# 16_VibrationdriverMod.net
KiCad netlist of a schematic drawn in EAGLE
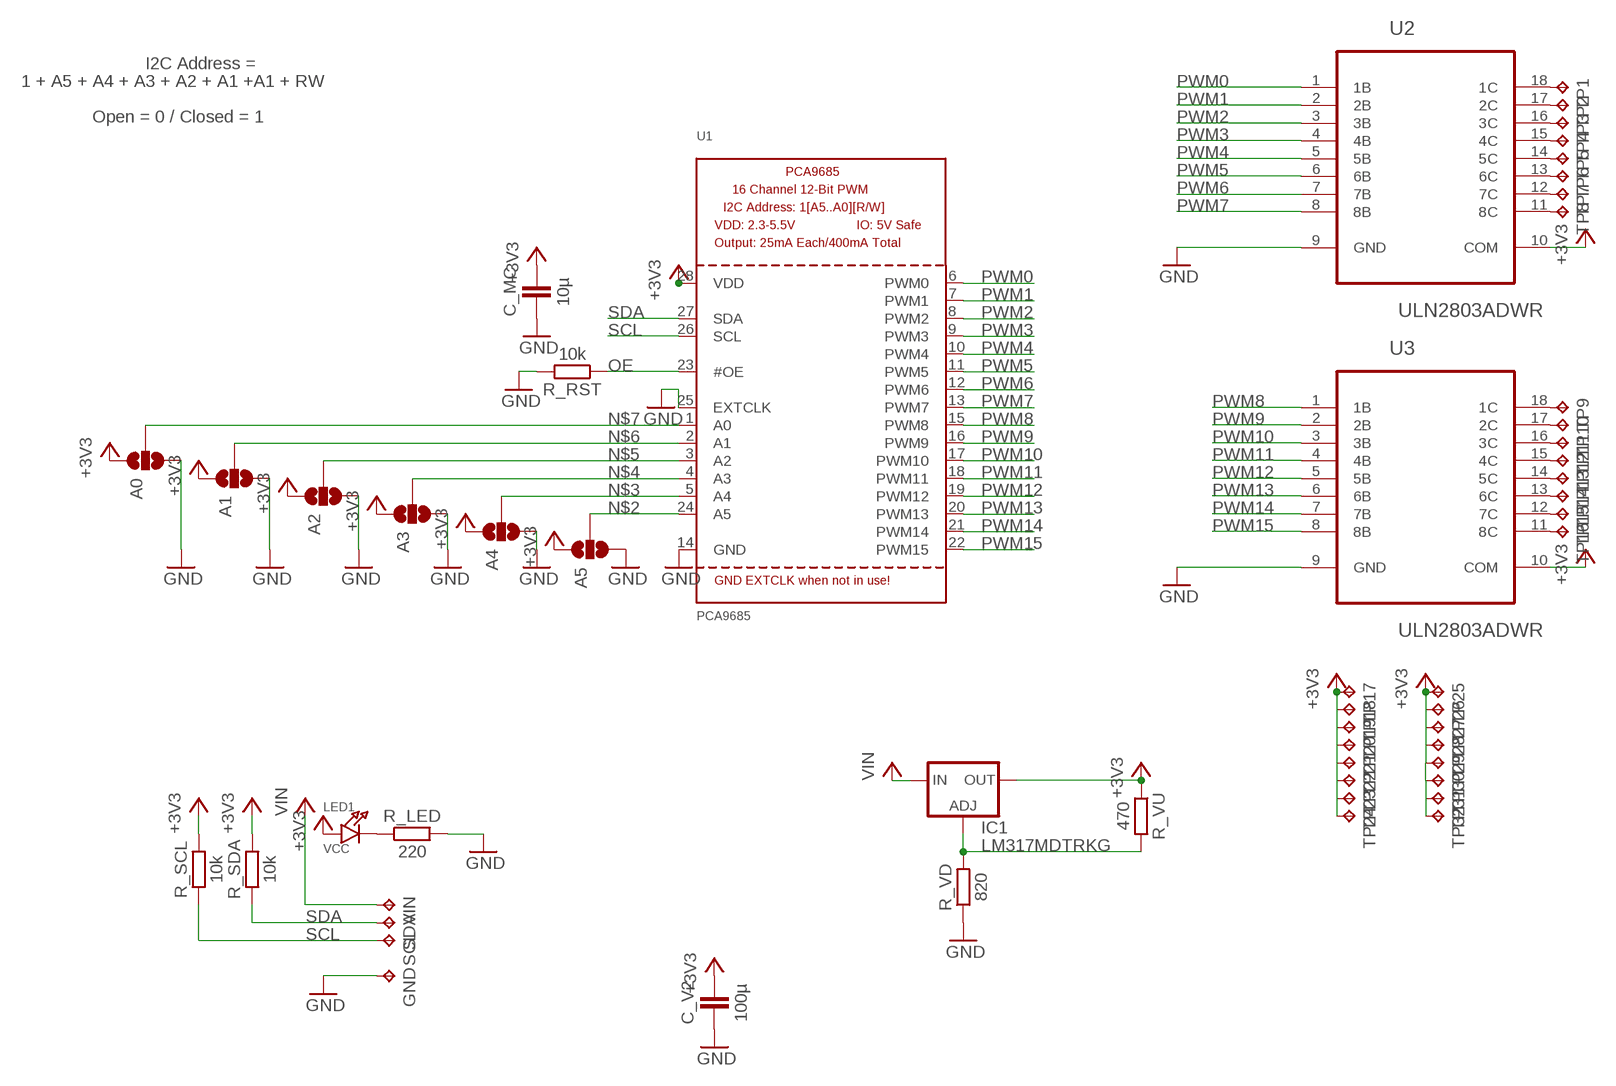
[diagram p0: schematic, sheet 1]

(export (version "E")
  (design (tool "Eeschema 10.0.6"))
  (components
    (comp (ref "A0")
      (value "SOLDERJUMPER_2WAYPASTE2&3")
      (footprint "eagle-import:SJ_3_PASTE2&3")
      (libsource (lib "eagle-import") (part "SOLDERJUMPER_2WAYPASTE2&3"))
    )
    (comp (ref "A1")
      (value "SOLDERJUMPER_2WAYPASTE2&3")
      (footprint "eagle-import:SJ_3_PASTE2&3")
      (libsource (lib "eagle-import") (part "SOLDERJUMPER_2WAYPASTE2&3"))
    )
    (comp (ref "A2")
      (value "SOLDERJUMPER_2WAYPASTE2&3")
      (footprint "eagle-import:SJ_3_PASTE2&3")
      (libsource (lib "eagle-import") (part "SOLDERJUMPER_2WAYPASTE2&3"))
    )
    (comp (ref "A3")
      (value "SOLDERJUMPER_2WAYPASTE2&3")
      (footprint "eagle-import:SJ_3_PASTE2&3")
      (libsource (lib "eagle-import") (part "SOLDERJUMPER_2WAYPASTE2&3"))
    )
    (comp (ref "A4")
      (value "SOLDERJUMPER_2WAYPASTE2&3")
      (footprint "eagle-import:SJ_3_PASTE2&3")
      (libsource (lib "eagle-import") (part "SOLDERJUMPER_2WAYPASTE2&3"))
    )
    (comp (ref "A5")
      (value "SOLDERJUMPER_2WAYPASTE2&3")
      (footprint "eagle-import:SJ_3_PASTE2&3")
      (libsource (lib "eagle-import") (part "SOLDERJUMPER_2WAYPASTE2&3"))
    )
    (comp (ref "C_MC")
      (value "10µ")
      (footprint "eagle-import:603")
      (libsource (lib "eagle-import") (part "CAPACITOR"))
    )
    (comp (ref "C_V2")
      (value "100µ")
      (footprint "eagle-import:1206")
      (libsource (lib "eagle-import") (part "CAPACITOR1206"))
    )
    (comp (ref "GND")
      (value "TPTP16SQ")
      (footprint "eagle-import:TP16SQ")
      (libsource (lib "eagle-import") (part "TPTP16SQ"))
    )
    (comp (ref "IC1")
      (value "LM317MDTRKG")
      (footprint "eagle-import:DPACK")
      (libsource (lib "eagle-import") (part "LM317?MDTRKG"))
    )
    (comp (ref "LED1")
      (value "VCC")
      (footprint "eagle-import:CHIPLED_0603")
      (libsource (lib "eagle-import") (part "LED0603"))
    )
    (comp (ref "R_LED")
      (value "220")
      (footprint "eagle-import:603")
      (libsource (lib "eagle-import") (part "RESISTOR0603"))
    )
    (comp (ref "R_RST")
      (value "10k")
      (footprint "eagle-import:603")
      (libsource (lib "eagle-import") (part "RESISTOR0603"))
    )
    (comp (ref "R_SCL")
      (value "10k")
      (footprint "eagle-import:603")
      (libsource (lib "eagle-import") (part "RESISTOR0603"))
    )
    (comp (ref "R_SDA")
      (value "10k")
      (footprint "eagle-import:603")
      (libsource (lib "eagle-import") (part "RESISTOR0603"))
    )
    (comp (ref "R_VD")
      (value "820")
      (footprint "eagle-import:603")
      (libsource (lib "eagle-import") (part "RESISTOR0603"))
    )
    (comp (ref "R_VU")
      (value "470")
      (footprint "eagle-import:603")
      (libsource (lib "eagle-import") (part "RESISTOR0603"))
    )
    (comp (ref "SCL")
      (value "TPTP16SQ")
      (footprint "eagle-import:TP16SQ")
      (libsource (lib "eagle-import") (part "TPTP16SQ"))
    )
    (comp (ref "SDA")
      (value "TPTP16SQ")
      (footprint "eagle-import:TP16SQ")
      (libsource (lib "eagle-import") (part "TPTP16SQ"))
    )
    (comp (ref "TP1")
      (value "TPTP16SQ")
      (footprint "eagle-import:TP16SQ")
      (libsource (lib "eagle-import") (part "TPTP16SQ"))
    )
    (comp (ref "TP2")
      (value "TPTP16SQ")
      (footprint "eagle-import:TP16SQ")
      (libsource (lib "eagle-import") (part "TPTP16SQ"))
    )
    (comp (ref "TP3")
      (value "TPTP16SQ")
      (footprint "eagle-import:TP16SQ")
      (libsource (lib "eagle-import") (part "TPTP16SQ"))
    )
    (comp (ref "TP4")
      (value "TPTP16SQ")
      (footprint "eagle-import:TP16SQ")
      (libsource (lib "eagle-import") (part "TPTP16SQ"))
    )
    (comp (ref "TP5")
      (value "TPTP16SQ")
      (footprint "eagle-import:TP16SQ")
      (libsource (lib "eagle-import") (part "TPTP16SQ"))
    )
    (comp (ref "TP6")
      (value "TPTP16SQ")
      (footprint "eagle-import:TP16SQ")
      (libsource (lib "eagle-import") (part "TPTP16SQ"))
    )
    (comp (ref "TP7")
      (value "TPTP16SQ")
      (footprint "eagle-import:TP16SQ")
      (libsource (lib "eagle-import") (part "TPTP16SQ"))
    )
    (comp (ref "TP8")
      (value "TPTP16SQ")
      (footprint "eagle-import:TP16SQ")
      (libsource (lib "eagle-import") (part "TPTP16SQ"))
    )
    (comp (ref "TP9")
      (value "TPTP16SQ")
      (footprint "eagle-import:TP16SQ")
      (libsource (lib "eagle-import") (part "TPTP16SQ"))
    )
    (comp (ref "TP10")
      (value "TPTP16SQ")
      (footprint "eagle-import:TP16SQ")
      (libsource (lib "eagle-import") (part "TPTP16SQ"))
    )
    (comp (ref "TP11")
      (value "TPTP16SQ")
      (footprint "eagle-import:TP16SQ")
      (libsource (lib "eagle-import") (part "TPTP16SQ"))
    )
    (comp (ref "TP12")
      (value "TPTP16SQ")
      (footprint "eagle-import:TP16SQ")
      (libsource (lib "eagle-import") (part "TPTP16SQ"))
    )
    (comp (ref "TP13")
      (value "TPTP16SQ")
      (footprint "eagle-import:TP16SQ")
      (libsource (lib "eagle-import") (part "TPTP16SQ"))
    )
    (comp (ref "TP14")
      (value "TPTP16SQ")
      (footprint "eagle-import:TP16SQ")
      (libsource (lib "eagle-import") (part "TPTP16SQ"))
    )
    (comp (ref "TP15")
      (value "TPTP16SQ")
      (footprint "eagle-import:TP16SQ")
      (libsource (lib "eagle-import") (part "TPTP16SQ"))
    )
    (comp (ref "TP16")
      (value "TPTP16SQ")
      (footprint "eagle-import:TP16SQ")
      (libsource (lib "eagle-import") (part "TPTP16SQ"))
    )
    (comp (ref "TP17")
      (value "TPTP16SQ")
      (footprint "eagle-import:TP16SQ")
      (libsource (lib "eagle-import") (part "TPTP16SQ"))
    )
    (comp (ref "TP18")
      (value "TPTP16SQ")
      (footprint "eagle-import:TP16SQ")
      (libsource (lib "eagle-import") (part "TPTP16SQ"))
    )
    (comp (ref "TP19")
      (value "TPTP16SQ")
      (footprint "eagle-import:TP16SQ")
      (libsource (lib "eagle-import") (part "TPTP16SQ"))
    )
    (comp (ref "TP20")
      (value "TPTP16SQ")
      (footprint "eagle-import:TP16SQ")
      (libsource (lib "eagle-import") (part "TPTP16SQ"))
    )
    (comp (ref "TP21")
      (value "TPTP16SQ")
      (footprint "eagle-import:TP16SQ")
      (libsource (lib "eagle-import") (part "TPTP16SQ"))
    )
    (comp (ref "TP22")
      (value "TPTP16SQ")
      (footprint "eagle-import:TP16SQ")
      (libsource (lib "eagle-import") (part "TPTP16SQ"))
    )
    (comp (ref "TP23")
      (value "TPTP16SQ")
      (footprint "eagle-import:TP16SQ")
      (libsource (lib "eagle-import") (part "TPTP16SQ"))
    )
    (comp (ref "TP24")
      (value "TPTP16SQ")
      (footprint "eagle-import:TP16SQ")
      (libsource (lib "eagle-import") (part "TPTP16SQ"))
    )
    (comp (ref "TP25")
      (value "TPTP16SQ")
      (footprint "eagle-import:TP16SQ")
      (libsource (lib "eagle-import") (part "TPTP16SQ"))
    )
    (comp (ref "TP26")
      (value "TPTP16SQ")
      (footprint "eagle-import:TP16SQ")
      (libsource (lib "eagle-import") (part "TPTP16SQ"))
    )
    (comp (ref "TP27")
      (value "TPTP16SQ")
      (footprint "eagle-import:TP16SQ")
      (libsource (lib "eagle-import") (part "TPTP16SQ"))
    )
    (comp (ref "TP28")
      (value "TPTP16SQ")
      (footprint "eagle-import:TP16SQ")
      (libsource (lib "eagle-import") (part "TPTP16SQ"))
    )
    (comp (ref "TP29")
      (value "TPTP16SQ")
      (footprint "eagle-import:TP16SQ")
      (libsource (lib "eagle-import") (part "TPTP16SQ"))
    )
    (comp (ref "TP30")
      (value "TPTP16SQ")
      (footprint "eagle-import:TP16SQ")
      (libsource (lib "eagle-import") (part "TPTP16SQ"))
    )
    (comp (ref "TP31")
      (value "TPTP16SQ")
      (footprint "eagle-import:TP16SQ")
      (libsource (lib "eagle-import") (part "TPTP16SQ"))
    )
    (comp (ref "TP32")
      (value "TPTP16SQ")
      (footprint "eagle-import:TP16SQ")
      (libsource (lib "eagle-import") (part "TPTP16SQ"))
    )
    (comp (ref "U1")
      (value "PCA9685")
      (footprint "eagle-import:TSSOP28")
      (libsource (lib "eagle-import") (part "PCA9685"))
    )
    (comp (ref "U2")
      (value "ULN2803ADWR")
      (footprint "eagle-import:SOIC127P1030X265-18N")
      (libsource (lib "eagle-import") (part "ULN2803ADWR"))
    )
    (comp (ref "U3")
      (value "ULN2803ADWR")
      (footprint "eagle-import:SOIC127P1030X265-18N")
      (libsource (lib "eagle-import") (part "ULN2803ADWR"))
    )
    (comp (ref "VIN")
      (value "TPTP16SQ")
      (footprint "eagle-import:TP16SQ")
      (libsource (lib "eagle-import") (part "TPTP16SQ"))
    )
  )
  (nets
    (net (code "1") (name "+3V3") (class "Default")
      (node (ref "A0") (pin "1") (pinfunction "1_1") (pintype "passive"))
      (node (ref "A1") (pin "1") (pinfunction "1_1") (pintype "passive"))
      (node (ref "A2") (pin "1") (pinfunction "1_1") (pintype "passive"))
      (node (ref "A3") (pin "1") (pinfunction "1_1") (pintype "passive"))
      (node (ref "A4") (pin "1") (pinfunction "1_1") (pintype "passive"))
      (node (ref "A5") (pin "1") (pinfunction "1_1") (pintype "passive"))
      (node (ref "C_MC") (pin "2") (pinfunction "2_2") (pintype "passive"))
      (node (ref "C_V2") (pin "2") (pinfunction "2_2") (pintype "passive"))
      (node (ref "IC1") (pin "4") (pinfunction "OUT_4") (pintype "passive"))
      (node (ref "LED1") (pin "A") (pinfunction "A_A") (pintype "passive"))
      (node (ref "R_SCL") (pin "2") (pinfunction "2_2") (pintype "passive"))
      (node (ref "R_SDA") (pin "2") (pinfunction "2_2") (pintype "passive"))
      (node (ref "R_VU") (pin "1") (pinfunction "1_1") (pintype "passive"))
      (node (ref "TP17") (pin "TP") (pinfunction "TP_TP") (pintype "input"))
      (node (ref "TP18") (pin "TP") (pinfunction "TP_TP") (pintype "input"))
      (node (ref "TP19") (pin "TP") (pinfunction "TP_TP") (pintype "input"))
      (node (ref "TP20") (pin "TP") (pinfunction "TP_TP") (pintype "input"))
      (node (ref "TP21") (pin "TP") (pinfunction "TP_TP") (pintype "input"))
      (node (ref "TP22") (pin "TP") (pinfunction "TP_TP") (pintype "input"))
      (node (ref "TP23") (pin "TP") (pinfunction "TP_TP") (pintype "input"))
      (node (ref "TP24") (pin "TP") (pinfunction "TP_TP") (pintype "input"))
      (node (ref "TP25") (pin "TP") (pinfunction "TP_TP") (pintype "input"))
      (node (ref "TP26") (pin "TP") (pinfunction "TP_TP") (pintype "input"))
      (node (ref "TP27") (pin "TP") (pinfunction "TP_TP") (pintype "input"))
      (node (ref "TP28") (pin "TP") (pinfunction "TP_TP") (pintype "input"))
      (node (ref "TP29") (pin "TP") (pinfunction "TP_TP") (pintype "input"))
      (node (ref "TP30") (pin "TP") (pinfunction "TP_TP") (pintype "input"))
      (node (ref "TP31") (pin "TP") (pinfunction "TP_TP") (pintype "input"))
      (node (ref "TP32") (pin "TP") (pinfunction "TP_TP") (pintype "input"))
      (node (ref "U1") (pin "28") (pinfunction "VDD_28") (pintype "power_in"))
      (node (ref "U2") (pin "10") (pinfunction "COM_10") (pintype "output"))
      (node (ref "U3") (pin "10") (pinfunction "COM_10") (pintype "output"))
    )
    (net (code "2") (name "/N$2") (class "Default")
      (node (ref "A5") (pin "2") (pinfunction "2_2") (pintype "passive"))
      (node (ref "U1") (pin "24") (pinfunction "A5_24") (pintype "bidirectional"))
    )
    (net (code "3") (name "/N$3") (class "Default")
      (node (ref "A4") (pin "2") (pinfunction "2_2") (pintype "passive"))
      (node (ref "U1") (pin "5") (pinfunction "A4_5") (pintype "bidirectional"))
    )
    (net (code "4") (name "/N$4") (class "Default")
      (node (ref "A3") (pin "2") (pinfunction "2_2") (pintype "passive"))
      (node (ref "U1") (pin "4") (pinfunction "A3_4") (pintype "bidirectional"))
    )
    (net (code "5") (name "/N$5") (class "Default")
      (node (ref "A2") (pin "2") (pinfunction "2_2") (pintype "passive"))
      (node (ref "U1") (pin "3") (pinfunction "A2_3") (pintype "bidirectional"))
    )
    (net (code "6") (name "/N$6") (class "Default")
      (node (ref "A1") (pin "2") (pinfunction "2_2") (pintype "passive"))
      (node (ref "U1") (pin "2") (pinfunction "A1_2") (pintype "bidirectional"))
    )
    (net (code "7") (name "/N$7") (class "Default")
      (node (ref "A0") (pin "2") (pinfunction "2_2") (pintype "passive"))
      (node (ref "U1") (pin "1") (pinfunction "A0_1") (pintype "bidirectional"))
    )
    (net (code "8") (name "/OE") (class "Default")
      (node (ref "R_RST") (pin "1") (pinfunction "1_1") (pintype "passive"))
      (node (ref "U1") (pin "23") (pinfunction "#OE_23") (pintype "input"))
    )
    (net (code "9") (name "/PWM0") (class "Default")
      (node (ref "U1") (pin "6") (pinfunction "PWM0_6") (pintype "output"))
      (node (ref "U2") (pin "1") (pinfunction "1B_1") (pintype "input"))
    )
    (net (code "10") (name "/PWM1") (class "Default")
      (node (ref "U1") (pin "7") (pinfunction "PWM1_7") (pintype "output"))
      (node (ref "U2") (pin "2") (pinfunction "2B_2") (pintype "input"))
    )
    (net (code "11") (name "/PWM2") (class "Default")
      (node (ref "U1") (pin "8") (pinfunction "PWM2_8") (pintype "output"))
      (node (ref "U2") (pin "3") (pinfunction "3B_3") (pintype "input"))
    )
    (net (code "12") (name "/PWM3") (class "Default")
      (node (ref "U1") (pin "9") (pinfunction "PWM3_9") (pintype "output"))
      (node (ref "U2") (pin "4") (pinfunction "4B_4") (pintype "input"))
    )
    (net (code "13") (name "/PWM4") (class "Default")
      (node (ref "U1") (pin "10") (pinfunction "PWM4_10") (pintype "output"))
      (node (ref "U2") (pin "5") (pinfunction "5B_5") (pintype "input"))
    )
    (net (code "14") (name "/PWM5") (class "Default")
      (node (ref "U1") (pin "11") (pinfunction "PWM5_11") (pintype "output"))
      (node (ref "U2") (pin "6") (pinfunction "6B_6") (pintype "input"))
    )
    (net (code "15") (name "/PWM6") (class "Default")
      (node (ref "U1") (pin "12") (pinfunction "PWM6_12") (pintype "output"))
      (node (ref "U2") (pin "7") (pinfunction "7B_7") (pintype "input"))
    )
    (net (code "16") (name "/PWM7") (class "Default")
      (node (ref "U1") (pin "13") (pinfunction "PWM7_13") (pintype "output"))
      (node (ref "U2") (pin "8") (pinfunction "8B_8") (pintype "input"))
    )
    (net (code "17") (name "/PWM8") (class "Default")
      (node (ref "U1") (pin "15") (pinfunction "PWM8_15") (pintype "output"))
      (node (ref "U3") (pin "1") (pinfunction "1B_1") (pintype "input"))
    )
    (net (code "18") (name "/PWM9") (class "Default")
      (node (ref "U1") (pin "16") (pinfunction "PWM9_16") (pintype "output"))
      (node (ref "U3") (pin "2") (pinfunction "2B_2") (pintype "input"))
    )
    (net (code "19") (name "/PWM10") (class "Default")
      (node (ref "U1") (pin "17") (pinfunction "PWM10_17") (pintype "output"))
      (node (ref "U3") (pin "3") (pinfunction "3B_3") (pintype "input"))
    )
    (net (code "20") (name "/PWM11") (class "Default")
      (node (ref "U1") (pin "18") (pinfunction "PWM11_18") (pintype "output"))
      (node (ref "U3") (pin "4") (pinfunction "4B_4") (pintype "input"))
    )
    (net (code "21") (name "/PWM12") (class "Default")
      (node (ref "U1") (pin "19") (pinfunction "PWM12_19") (pintype "output"))
      (node (ref "U3") (pin "5") (pinfunction "5B_5") (pintype "input"))
    )
    (net (code "22") (name "/PWM13") (class "Default")
      (node (ref "U1") (pin "20") (pinfunction "PWM13_20") (pintype "output"))
      (node (ref "U3") (pin "6") (pinfunction "6B_6") (pintype "input"))
    )
    (net (code "23") (name "/PWM14") (class "Default")
      (node (ref "U1") (pin "21") (pinfunction "PWM14_21") (pintype "output"))
      (node (ref "U3") (pin "7") (pinfunction "7B_7") (pintype "input"))
    )
    (net (code "24") (name "/PWM15") (class "Default")
      (node (ref "U1") (pin "22") (pinfunction "PWM15_22") (pintype "output"))
      (node (ref "U3") (pin "8") (pinfunction "8B_8") (pintype "input"))
    )
    (net (code "25") (name "/SCL") (class "Default")
      (node (ref "R_SCL") (pin "1") (pinfunction "1_1") (pintype "passive"))
      (node (ref "SCL") (pin "TP") (pinfunction "TP_TP") (pintype "input"))
      (node (ref "U1") (pin "26") (pinfunction "SCL_26") (pintype "bidirectional"))
    )
    (net (code "26") (name "/SDA") (class "Default")
      (node (ref "R_SDA") (pin "1") (pinfunction "1_1") (pintype "passive"))
      (node (ref "SDA") (pin "TP") (pinfunction "TP_TP") (pintype "input"))
      (node (ref "U1") (pin "27") (pinfunction "SDA_27") (pintype "bidirectional"))
    )
    (net (code "27") (name "GND") (class "Default")
      (node (ref "A0") (pin "3") (pinfunction "3_3") (pintype "passive"))
      (node (ref "A1") (pin "3") (pinfunction "3_3") (pintype "passive"))
      (node (ref "A2") (pin "3") (pinfunction "3_3") (pintype "passive"))
      (node (ref "A3") (pin "3") (pinfunction "3_3") (pintype "passive"))
      (node (ref "A4") (pin "3") (pinfunction "3_3") (pintype "passive"))
      (node (ref "A5") (pin "3") (pinfunction "3_3") (pintype "passive"))
      (node (ref "C_MC") (pin "1") (pinfunction "1_1") (pintype "passive"))
      (node (ref "C_V2") (pin "1") (pinfunction "1_1") (pintype "passive"))
      (node (ref "GND") (pin "TP") (pinfunction "TP_TP") (pintype "input"))
      (node (ref "R_LED") (pin "2") (pinfunction "2_2") (pintype "passive"))
      (node (ref "R_RST") (pin "2") (pinfunction "2_2") (pintype "passive"))
      (node (ref "R_VD") (pin "1") (pinfunction "1_1") (pintype "passive"))
      (node (ref "U1") (pin "14") (pinfunction "GND_14") (pintype "power_in"))
      (node (ref "U1") (pin "25") (pinfunction "EXTCLK_25") (pintype "input"))
      (node (ref "U2") (pin "9") (pinfunction "GND_9") (pintype "passive"))
      (node (ref "U3") (pin "9") (pinfunction "GND_9") (pintype "passive"))
    )
    (net (code "28") (name "Net-(IC1-ADJ)") (class "Default")
      (node (ref "IC1") (pin "1") (pinfunction "ADJ_1") (pintype "input"))
      (node (ref "R_VD") (pin "2") (pinfunction "2_2") (pintype "passive"))
      (node (ref "R_VU") (pin "2") (pinfunction "2_2") (pintype "passive"))
    )
    (net (code "29") (name "Net-(LED1-PadC)") (class "Default")
      (node (ref "LED1") (pin "C") (pinfunction "C_C") (pintype "passive"))
      (node (ref "R_LED") (pin "1") (pinfunction "1_1") (pintype "passive"))
    )
    (net (code "30") (name "Net-(U2-1C)") (class "Default")
      (node (ref "TP1") (pin "TP") (pinfunction "TP_TP") (pintype "input"))
      (node (ref "U2") (pin "18") (pinfunction "1C_18") (pintype "output"))
    )
    (net (code "31") (name "Net-(U2-2C)") (class "Default")
      (node (ref "TP2") (pin "TP") (pinfunction "TP_TP") (pintype "input"))
      (node (ref "U2") (pin "17") (pinfunction "2C_17") (pintype "output"))
    )
    (net (code "32") (name "Net-(U2-3C)") (class "Default")
      (node (ref "TP3") (pin "TP") (pinfunction "TP_TP") (pintype "input"))
      (node (ref "U2") (pin "16") (pinfunction "3C_16") (pintype "output"))
    )
    (net (code "33") (name "Net-(U2-4C)") (class "Default")
      (node (ref "TP4") (pin "TP") (pinfunction "TP_TP") (pintype "input"))
      (node (ref "U2") (pin "15") (pinfunction "4C_15") (pintype "output"))
    )
    (net (code "34") (name "Net-(U2-5C)") (class "Default")
      (node (ref "TP5") (pin "TP") (pinfunction "TP_TP") (pintype "input"))
      (node (ref "U2") (pin "14") (pinfunction "5C_14") (pintype "output"))
    )
    (net (code "35") (name "Net-(U2-6C)") (class "Default")
      (node (ref "TP6") (pin "TP") (pinfunction "TP_TP") (pintype "input"))
      (node (ref "U2") (pin "13") (pinfunction "6C_13") (pintype "output"))
    )
    (net (code "36") (name "Net-(U2-7C)") (class "Default")
      (node (ref "TP7") (pin "TP") (pinfunction "TP_TP") (pintype "input"))
      (node (ref "U2") (pin "12") (pinfunction "7C_12") (pintype "output"))
    )
    (net (code "37") (name "Net-(U2-8C)") (class "Default")
      (node (ref "TP8") (pin "TP") (pinfunction "TP_TP") (pintype "input"))
      (node (ref "U2") (pin "11") (pinfunction "8C_11") (pintype "output"))
    )
    (net (code "38") (name "Net-(U3-1C)") (class "Default")
      (node (ref "TP9") (pin "TP") (pinfunction "TP_TP") (pintype "input"))
      (node (ref "U3") (pin "18") (pinfunction "1C_18") (pintype "output"))
    )
    (net (code "39") (name "Net-(U3-2C)") (class "Default")
      (node (ref "TP10") (pin "TP") (pinfunction "TP_TP") (pintype "input"))
      (node (ref "U3") (pin "17") (pinfunction "2C_17") (pintype "output"))
    )
    (net (code "40") (name "Net-(U3-3C)") (class "Default")
      (node (ref "TP11") (pin "TP") (pinfunction "TP_TP") (pintype "input"))
      (node (ref "U3") (pin "16") (pinfunction "3C_16") (pintype "output"))
    )
    (net (code "41") (name "Net-(U3-4C)") (class "Default")
      (node (ref "TP12") (pin "TP") (pinfunction "TP_TP") (pintype "input"))
      (node (ref "U3") (pin "15") (pinfunction "4C_15") (pintype "output"))
    )
    (net (code "42") (name "Net-(U3-5C)") (class "Default")
      (node (ref "TP13") (pin "TP") (pinfunction "TP_TP") (pintype "input"))
      (node (ref "U3") (pin "14") (pinfunction "5C_14") (pintype "output"))
    )
    (net (code "43") (name "Net-(U3-6C)") (class "Default")
      (node (ref "TP14") (pin "TP") (pinfunction "TP_TP") (pintype "input"))
      (node (ref "U3") (pin "13") (pinfunction "6C_13") (pintype "output"))
    )
    (net (code "44") (name "Net-(U3-7C)") (class "Default")
      (node (ref "TP15") (pin "TP") (pinfunction "TP_TP") (pintype "input"))
      (node (ref "U3") (pin "12") (pinfunction "7C_12") (pintype "output"))
    )
    (net (code "45") (name "Net-(U3-8C)") (class "Default")
      (node (ref "TP16") (pin "TP") (pinfunction "TP_TP") (pintype "input"))
      (node (ref "U3") (pin "11") (pinfunction "8C_11") (pintype "output"))
    )
    (net (code "46") (name "VIN") (class "Default")
      (node (ref "IC1") (pin "3") (pinfunction "IN_3") (pintype "input"))
      (node (ref "VIN") (pin "TP") (pinfunction "TP_TP") (pintype "input"))
    )
  )
)
